# ESP8285_SMD_0603.net
KiCad netlist of a schematic drawn in EAGLE
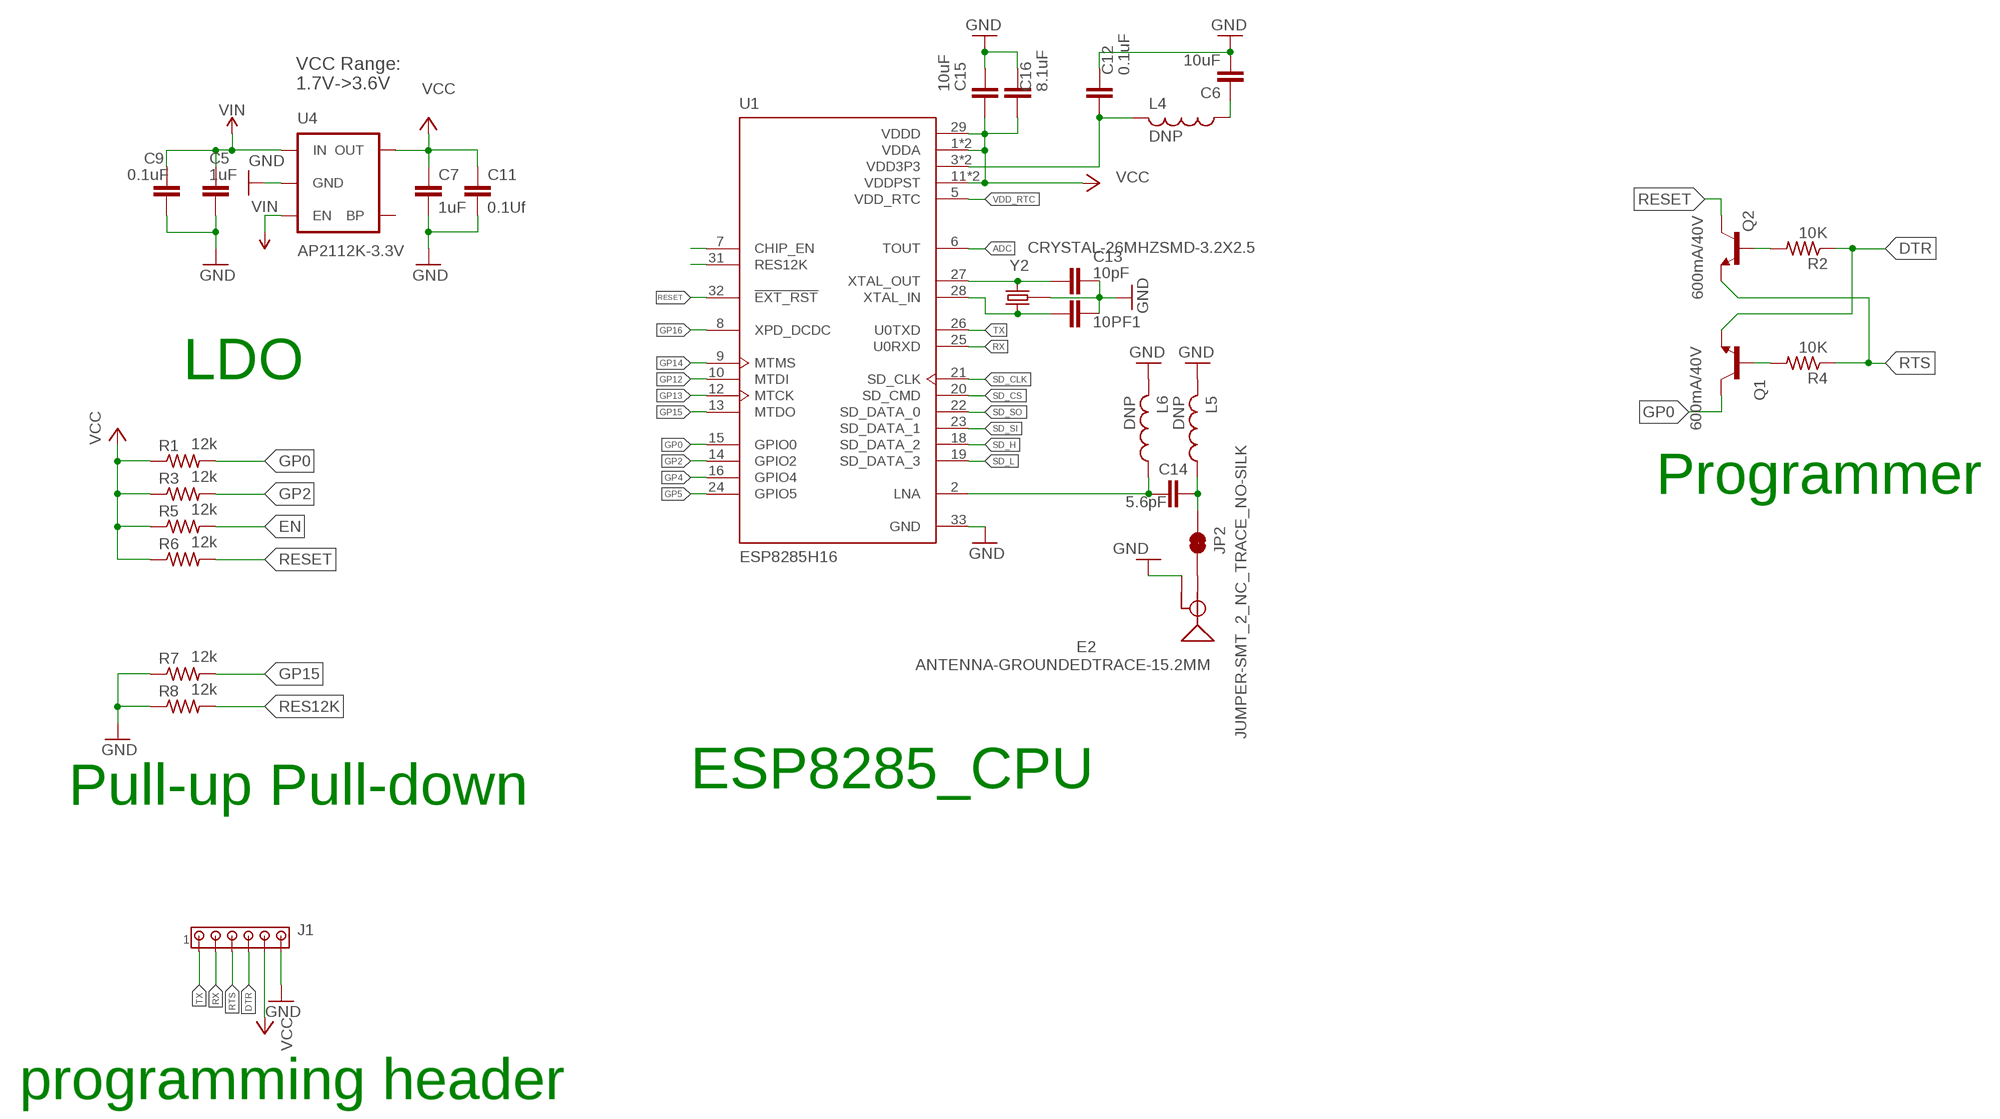
[diagram p0: schematic, sheet 1]

(export (version "E")
  (design (tool "Eeschema 10.0.6"))
  (components
    (comp (ref "10PF1")
      (value "C-EUC0603")
      (footprint "eagle-import:C0603")
      (libsource (lib "eagle-import") (part "C-EUC0603"))
    )
    (comp (ref "C5")
      (value "1uF")
      (footprint "eagle-import:C0603")
      (libsource (lib "eagle-import") (part "C-EUC0603"))
    )
    (comp (ref "C6")
      (value "10uF")
      (footprint "eagle-import:C0603")
      (libsource (lib "eagle-import") (part "C-EUC0603"))
    )
    (comp (ref "C7")
      (value "1uF")
      (footprint "eagle-import:C0603")
      (libsource (lib "eagle-import") (part "C-EUC0603"))
    )
    (comp (ref "C9")
      (value "0.1uF")
      (footprint "eagle-import:C0603")
      (libsource (lib "eagle-import") (part "C-EUC0603"))
    )
    (comp (ref "C11")
      (value "0.1Uf")
      (footprint "eagle-import:C0603")
      (libsource (lib "eagle-import") (part "C-EUC0603"))
    )
    (comp (ref "C12")
      (value "0.1uF")
      (footprint "eagle-import:C0603")
      (libsource (lib "eagle-import") (part "C-EUC0603"))
    )
    (comp (ref "C13")
      (value "10pF")
      (footprint "eagle-import:C0603")
      (libsource (lib "eagle-import") (part "C-EUC0603"))
    )
    (comp (ref "C14")
      (value "5.6pF")
      (footprint "eagle-import:C0603")
      (libsource (lib "eagle-import") (part "C-EUC0603"))
    )
    (comp (ref "C15")
      (value "10uF")
      (footprint "eagle-import:C0603")
      (libsource (lib "eagle-import") (part "C-EUC0603"))
    )
    (comp (ref "C16")
      (value "8.1uF")
      (footprint "eagle-import:C0603")
      (libsource (lib "eagle-import") (part "C-EUC0603"))
    )
    (comp (ref "E2")
      (value "ANTENNA-GROUNDEDTRACE-15.2MM")
      (footprint "eagle-import:TRACE_ANTENNA_2.4GHZ_15.2MM")
      (libsource (lib "eagle-import") (part "ANTENNA-GROUNDEDTRACE-15.2MM"))
    )
    (comp (ref "J1")
      (value "MTA06-100")
      (footprint "eagle-import:10X06MTA")
      (libsource (lib "eagle-import") (part "MTA06-100"))
    )
    (comp (ref "JP2")
      (value "JUMPER-SMT_2_NC_TRACE_NO-SILK")
      (footprint "eagle-import:SMT-JUMPER_2_NC_TRACE_NO-SILK")
      (libsource (lib "eagle-import") (part "JUMPER-SMT_2_NC_TRACE_NO-SILK"))
    )
    (comp (ref "L4")
      (value "DNP")
      (footprint "eagle-import:L0603")
      (libsource (lib "eagle-import") (part "L-USL0603"))
    )
    (comp (ref "L5")
      (value "DNP")
      (footprint "eagle-import:L0603")
      (libsource (lib "eagle-import") (part "L-USL0603"))
    )
    (comp (ref "L6")
      (value "DNP")
      (footprint "eagle-import:L0603")
      (libsource (lib "eagle-import") (part "L-USL0603"))
    )
    (comp (ref "Q1")
      (value "600mA/40V")
      (footprint "eagle-import:SOT23-3")
      (libsource (lib "eagle-import") (part "TRANS_NPN-MMBT2222AL"))
    )
    (comp (ref "Q2")
      (value "600mA/40V")
      (footprint "eagle-import:SOT23-3")
      (libsource (lib "eagle-import") (part "TRANS_NPN-MMBT2222AL"))
    )
    (comp (ref "R1")
      (value "12k")
      (footprint "eagle-import:R0603")
      (libsource (lib "eagle-import") (part "rcl-2_R-US_R0603"))
    )
    (comp (ref "R2")
      (value "10K")
      (footprint "eagle-import:R0603")
      (libsource (lib "eagle-import") (part "R-US_R0603"))
    )
    (comp (ref "R3")
      (value "12k")
      (footprint "eagle-import:R0603")
      (libsource (lib "eagle-import") (part "rcl-2_R-US_R0603"))
    )
    (comp (ref "R4")
      (value "10K")
      (footprint "eagle-import:R0603")
      (libsource (lib "eagle-import") (part "R-US_R0603"))
    )
    (comp (ref "R5")
      (value "12k")
      (footprint "eagle-import:R0603")
      (libsource (lib "eagle-import") (part "rcl-2_R-US_R0603"))
    )
    (comp (ref "R6")
      (value "12k")
      (footprint "eagle-import:R0603")
      (libsource (lib "eagle-import") (part "rcl-2_R-US_R0603"))
    )
    (comp (ref "R7")
      (value "12k")
      (footprint "eagle-import:R0603")
      (libsource (lib "eagle-import") (part "rcl-2_R-US_R0603"))
    )
    (comp (ref "R8")
      (value "12k")
      (footprint "eagle-import:R0603")
      (libsource (lib "eagle-import") (part "rcl-2_R-US_R0603"))
    )
    (comp (ref "U1")
      (value "ESP8285H16")
      (footprint "eagle-import:QFN50P500X500X90-33N")
      (fields (field (name "MF") "Espressif Systems"))
      (libsource (lib "eagle-import") (part "ESP8285H16"))
    )
    (comp (ref "U4")
      (value "AP2112K-3.3V")
      (footprint "eagle-import:SOT23-5")
      (libsource (lib "eagle-import") (part "V_REG_LDOSMD"))
    )
    (comp (ref "Y2")
      (value "CRYSTAL-26MHZSMD-3.2X2.5")
      (footprint "eagle-import:CRYSTAL-SMD-3.2X2.5MM")
      (libsource (lib "eagle-import") (part "CRYSTAL-26MHZSMD-3.2X2.5"))
    )
  )
  (nets
    (net (code "1") (name "ADC") (class "Default")
      (node (ref "U1") (pin "6") (pinfunction "TOUT_6") (pintype "output"))
    )
    (net (code "2") (name "DTR") (class "Default")
      (node (ref "J1") (pin "4") (pinfunction "4_4") (pintype "passive"))
      (node (ref "Q1") (pin "2") (pinfunction "E_2") (pintype "passive"))
      (node (ref "R2") (pin "1") (pinfunction "1_1") (pintype "passive"))
    )
    (net (code "3") (name "EN") (class "Default")
      (node (ref "R5") (pin "2") (pinfunction "2_2") (pintype "passive"))
    )
    (net (code "4") (name "GND") (class "Default")
      (node (ref "10PF1") (pin "1") (pinfunction "1_1") (pintype "passive"))
      (node (ref "C11") (pin "2") (pinfunction "2_2") (pintype "passive"))
      (node (ref "C12") (pin "2") (pinfunction "2_2") (pintype "passive"))
      (node (ref "C13") (pin "1") (pinfunction "1_1") (pintype "passive"))
      (node (ref "C15") (pin "1") (pinfunction "1_1") (pintype "passive"))
      (node (ref "C16") (pin "1") (pinfunction "1_1") (pintype "passive"))
      (node (ref "C5") (pin "2") (pinfunction "2_2") (pintype "passive"))
      (node (ref "C6") (pin "2") (pinfunction "2_2") (pintype "passive"))
      (node (ref "C7") (pin "2") (pinfunction "2_2") (pintype "passive"))
      (node (ref "C9") (pin "2") (pinfunction "2_2") (pintype "passive"))
      (node (ref "E2") (pin "GND") (pinfunction "GND_GND") (pintype "bidirectional"))
      (node (ref "J1") (pin "6") (pinfunction "6_6") (pintype "passive"))
      (node (ref "L5") (pin "2") (pinfunction "2_2") (pintype "passive"))
      (node (ref "L6") (pin "2") (pinfunction "2_2") (pintype "passive"))
      (node (ref "R7") (pin "1") (pinfunction "1_1") (pintype "passive"))
      (node (ref "R8") (pin "1") (pinfunction "1_1") (pintype "passive"))
      (node (ref "U1") (pin "33") (pinfunction "GND_33") (pintype "power_in"))
      (node (ref "U4") (pin "2") (pinfunction "GND_2") (pintype "input"))
      (node (ref "Y2") (pin "2") (pinfunction "3_2") (pintype "passive"))
      (node (ref "Y2") (pin "4") (pinfunction "3_4") (pintype "passive"))
    )
    (net (code "5") (name "GP0") (class "Default")
      (node (ref "Q1") (pin "3") (pinfunction "C_3") (pintype "passive"))
      (node (ref "R1") (pin "2") (pinfunction "2_2") (pintype "passive"))
      (node (ref "U1") (pin "15") (pinfunction "GPIO0_15") (pintype "bidirectional"))
    )
    (net (code "6") (name "GP2") (class "Default")
      (node (ref "R3") (pin "2") (pinfunction "2_2") (pintype "passive"))
      (node (ref "U1") (pin "14") (pinfunction "GPIO2_14") (pintype "bidirectional"))
    )
    (net (code "7") (name "GP4") (class "Default")
      (node (ref "U1") (pin "16") (pinfunction "GPIO4_16") (pintype "bidirectional"))
    )
    (net (code "8") (name "GP5") (class "Default")
      (node (ref "U1") (pin "24") (pinfunction "GPIO5_24") (pintype "bidirectional"))
    )
    (net (code "9") (name "GP12") (class "Default")
      (node (ref "U1") (pin "10") (pinfunction "MTDI_10") (pintype "bidirectional"))
    )
    (net (code "10") (name "GP13") (class "Default")
      (node (ref "U1") (pin "12") (pinfunction "MTCK_12") (pintype "bidirectional"))
    )
    (net (code "11") (name "GP14") (class "Default")
      (node (ref "U1") (pin "9") (pinfunction "MTMS_9") (pintype "bidirectional"))
    )
    (net (code "12") (name "GP15") (class "Default")
      (node (ref "R7") (pin "2") (pinfunction "2_2") (pintype "passive"))
      (node (ref "U1") (pin "13") (pinfunction "MTDO_13") (pintype "bidirectional"))
    )
    (net (code "13") (name "GP16") (class "Default")
      (node (ref "U1") (pin "8") (pinfunction "XPD_DCDC_8") (pintype "bidirectional"))
    )
    (net (code "14") (name "Net-(C6-Pad1)") (class "Default")
      (node (ref "C6") (pin "1") (pinfunction "1_1") (pintype "passive"))
      (node (ref "L4") (pin "1") (pinfunction "1_1") (pintype "passive"))
    )
    (net (code "15") (name "Net-(C12-Pad1)") (class "Default")
      (node (ref "C12") (pin "1") (pinfunction "1_1") (pintype "passive"))
      (node (ref "L4") (pin "2") (pinfunction "2_2") (pintype "passive"))
      (node (ref "U1") (pin "3") (pinfunction "VDD3P3_3") (pintype "power_in"))
      (node (ref "U1") (pin "4") (pinfunction "VDD3P3_4") (pintype "power_in"))
    )
    (net (code "16") (name "Net-(C14-Pad1)") (class "Default")
      (node (ref "C14") (pin "1") (pinfunction "1_1") (pintype "passive"))
      (node (ref "JP2") (pin "1") (pinfunction "1_1") (pintype "passive"))
      (node (ref "L5") (pin "1") (pinfunction "1_1") (pintype "passive"))
    )
    (net (code "17") (name "Net-(E2-SIGNAL)") (class "Default")
      (node (ref "E2") (pin "ANT") (pinfunction "SIGNAL_ANT") (pintype "bidirectional"))
      (node (ref "JP2") (pin "2") (pinfunction "2_2") (pintype "passive"))
    )
    (net (code "18") (name "Net-(Q1-B)") (class "Default")
      (node (ref "Q1") (pin "1") (pinfunction "B_1") (pintype "passive"))
      (node (ref "R4") (pin "2") (pinfunction "2_2") (pintype "passive"))
    )
    (net (code "19") (name "Net-(Q2-B)") (class "Default")
      (node (ref "Q2") (pin "1") (pinfunction "B_1") (pintype "passive"))
      (node (ref "R2") (pin "2") (pinfunction "2_2") (pintype "passive"))
    )
    (net (code "20") (name "Net-(U1-LNA)") (class "Default")
      (node (ref "C14") (pin "2") (pinfunction "2_2") (pintype "passive"))
      (node (ref "L6") (pin "1") (pinfunction "1_1") (pintype "passive"))
      (node (ref "U1") (pin "2") (pinfunction "LNA_2") (pintype "bidirectional"))
    )
    (net (code "21") (name "Net-(U1-XTAL_IN)") (class "Default")
      (node (ref "10PF1") (pin "2") (pinfunction "2_2") (pintype "passive"))
      (node (ref "U1") (pin "28") (pinfunction "XTAL_IN_28") (pintype "input"))
      (node (ref "Y2") (pin "1") (pinfunction "1_1") (pintype "passive"))
    )
    (net (code "22") (name "Net-(U1-XTAL_OUT)") (class "Default")
      (node (ref "C13") (pin "2") (pinfunction "2_2") (pintype "passive"))
      (node (ref "U1") (pin "27") (pinfunction "XTAL_OUT_27") (pintype "output"))
      (node (ref "Y2") (pin "3") (pinfunction "2_3") (pintype "passive"))
    )
    (net (code "23") (name "RES12K") (class "Default")
      (node (ref "R8") (pin "2") (pinfunction "2_2") (pintype "passive"))
    )
    (net (code "24") (name "RESET") (class "Default")
      (node (ref "Q2") (pin "3") (pinfunction "C_3") (pintype "passive"))
      (node (ref "R6") (pin "2") (pinfunction "2_2") (pintype "passive"))
      (node (ref "U1") (pin "32") (pinfunction "~{EXT_RST}_32") (pintype "input"))
    )
    (net (code "25") (name "RTS") (class "Default")
      (node (ref "J1") (pin "3") (pinfunction "3_3") (pintype "passive"))
      (node (ref "Q2") (pin "2") (pinfunction "E_2") (pintype "passive"))
      (node (ref "R4") (pin "1") (pinfunction "1_1") (pintype "passive"))
    )
    (net (code "26") (name "RX") (class "Default")
      (node (ref "J1") (pin "2") (pinfunction "2_2") (pintype "passive"))
      (node (ref "U1") (pin "25") (pinfunction "U0RXD_25") (pintype "bidirectional"))
    )
    (net (code "27") (name "SD_CLK") (class "Default")
      (node (ref "U1") (pin "21") (pinfunction "SD_CLK_21") (pintype "bidirectional"))
    )
    (net (code "28") (name "SD_CS") (class "Default")
      (node (ref "U1") (pin "20") (pinfunction "SD_CMD_20") (pintype "bidirectional"))
    )
    (net (code "29") (name "SD_H") (class "Default")
      (node (ref "U1") (pin "18") (pinfunction "SD_DATA_2_18") (pintype "bidirectional"))
    )
    (net (code "30") (name "SD_L") (class "Default")
      (node (ref "U1") (pin "19") (pinfunction "SD_DATA_3_19") (pintype "bidirectional"))
    )
    (net (code "31") (name "SD_SI") (class "Default")
      (node (ref "U1") (pin "23") (pinfunction "SD_DATA_1_23") (pintype "bidirectional"))
    )
    (net (code "32") (name "SD_SO") (class "Default")
      (node (ref "U1") (pin "22") (pinfunction "SD_DATA_0_22") (pintype "bidirectional"))
    )
    (net (code "33") (name "TX") (class "Default")
      (node (ref "J1") (pin "1") (pinfunction "1_1") (pintype "passive"))
      (node (ref "U1") (pin "26") (pinfunction "U0TXD_26") (pintype "bidirectional"))
    )
    (net (code "34") (name "VCC") (class "Default")
      (node (ref "C11") (pin "1") (pinfunction "1_1") (pintype "passive"))
      (node (ref "C15") (pin "2") (pinfunction "2_2") (pintype "passive"))
      (node (ref "C16") (pin "2") (pinfunction "2_2") (pintype "passive"))
      (node (ref "C7") (pin "1") (pinfunction "1_1") (pintype "passive"))
      (node (ref "J1") (pin "5") (pinfunction "5_5") (pintype "passive"))
      (node (ref "R1") (pin "1") (pinfunction "1_1") (pintype "passive"))
      (node (ref "R3") (pin "1") (pinfunction "1_1") (pintype "passive"))
      (node (ref "R5") (pin "1") (pinfunction "1_1") (pintype "passive"))
      (node (ref "R6") (pin "1") (pinfunction "1_1") (pintype "passive"))
      (node (ref "U1") (pin "1") (pinfunction "VDDA_1") (pintype "power_in"))
      (node (ref "U1") (pin "11") (pinfunction "VDDPST_11") (pintype "power_in"))
      (node (ref "U1") (pin "17") (pinfunction "VDDPST_17") (pintype "power_in"))
      (node (ref "U1") (pin "29") (pinfunction "VDDD_29") (pintype "power_in"))
      (node (ref "U1") (pin "30") (pinfunction "VDDA_30") (pintype "power_in"))
      (node (ref "U4") (pin "5") (pinfunction "OUT_5") (pintype "passive"))
    )
    (net (code "35") (name "VDD_RTC") (class "Default")
      (node (ref "U1") (pin "5") (pinfunction "VDD_RTC_5") (pintype "power_in"))
    )
    (net (code "36") (name "VIN") (class "Default")
      (node (ref "C5") (pin "1") (pinfunction "1_1") (pintype "passive"))
      (node (ref "C9") (pin "1") (pinfunction "1_1") (pintype "passive"))
      (node (ref "U4") (pin "1") (pinfunction "IN_1") (pintype "input"))
      (node (ref "U4") (pin "3") (pinfunction "EN_3") (pintype "input"))
    )
    (net (code "37") (name "unconnected-(U1-CHIP_EN-Pad7)") (class "Default")
      (node (ref "U1") (pin "7") (pinfunction "CHIP_EN_7") (pintype "input"))
    )
    (net (code "38") (name "unconnected-(U1-RES12K-Pad31)") (class "Default")
      (node (ref "U1") (pin "31") (pinfunction "RES12K_31") (pintype "input"))
    )
    (net (code "39") (name "unconnected-(U4-BP-Pad4)") (class "Default")
      (node (ref "U4") (pin "4") (pinfunction "BP_4") (pintype "input"))
    )
  )
)
